# Front_left_lamp_v4.net
KiCad netlist of a schematic drawn in EAGLE
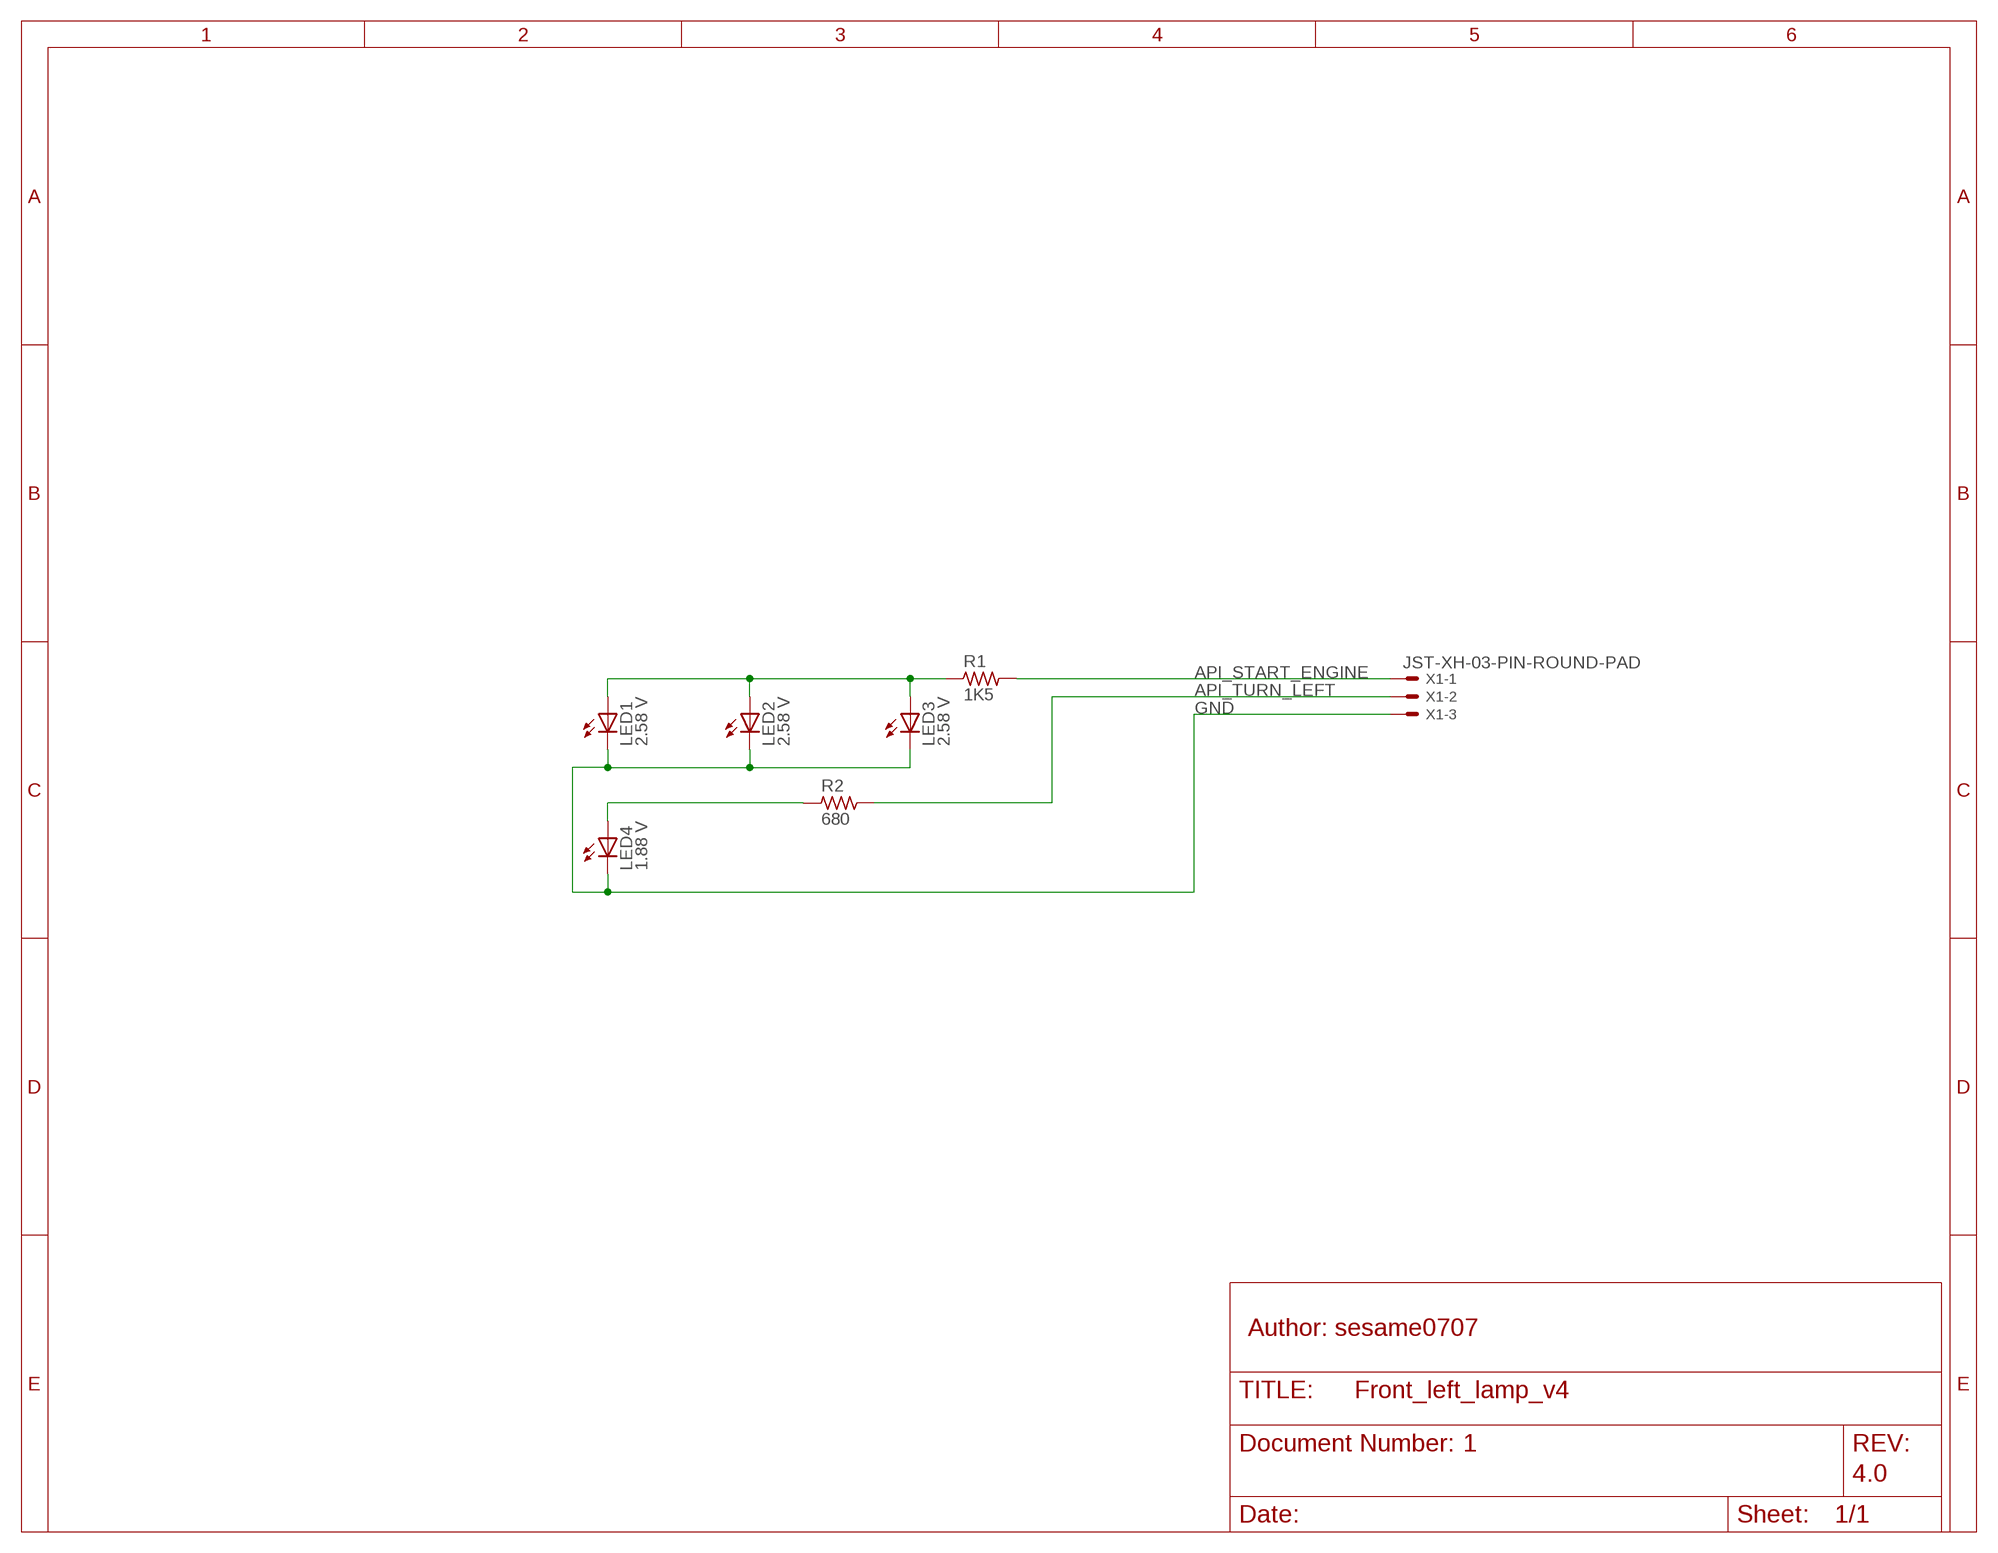
[diagram p0: schematic, sheet 1]

(export (version "E")
  (design (tool "Eeschema 10.0.6"))
  (components
    (comp (ref "LED1")
      (value "2.58 V")
      (footprint "eagle-import:LED5MM")
      (libsource (lib "eagle-import") (part "LED5MM"))
    )
    (comp (ref "LED2")
      (value "2.58 V")
      (footprint "eagle-import:LED5MM")
      (libsource (lib "eagle-import") (part "LED5MM"))
    )
    (comp (ref "LED3")
      (value "2.58 V")
      (footprint "eagle-import:LED5MM")
      (libsource (lib "eagle-import") (part "LED5MM"))
    )
    (comp (ref "LED4")
      (value "1.88 V")
      (footprint "eagle-import:LED5MM")
      (libsource (lib "eagle-import") (part "LED5MM"))
    )
    (comp (ref "R1")
      (value "1K5")
      (footprint "eagle-import:R1206")
      (libsource (lib "eagle-import") (part "R_1206"))
    )
    (comp (ref "R2")
      (value "680")
      (footprint "eagle-import:R1206")
      (libsource (lib "eagle-import") (part "R_1206"))
    )
    (comp (ref "X1")
      (value "JST-XH-03-PIN-ROUND-PAD")
      (footprint "eagle-import:JST-XH-03-PACKAGE-ROUND-PAD")
      (libsource (lib "eagle-import") (part "JST-XH-03-PIN-ROUND-PAD"))
    )
  )
  (nets
    (net (code "1") (name "/API_START_ENGINE") (class "Default")
      (node (ref "LED1") (pin "A") (pinfunction "A_A") (pintype "passive"))
      (node (ref "LED2") (pin "A") (pinfunction "A_A") (pintype "passive"))
      (node (ref "LED3") (pin "A") (pinfunction "A_A") (pintype "passive"))
      (node (ref "R1") (pin "1") (pinfunction "1_1") (pintype "passive"))
    )
    (net (code "2") (name "/API_TURN_LEFT") (class "Default")
      (node (ref "R2") (pin "2") (pinfunction "2_2") (pintype "passive"))
      (node (ref "X1") (pin "2") (pinfunction "S_2") (pintype "passive"))
    )
    (net (code "3") (name "/GND") (class "Default")
      (node (ref "LED1") (pin "K") (pinfunction "C_K") (pintype "passive"))
      (node (ref "LED2") (pin "K") (pinfunction "C_K") (pintype "passive"))
      (node (ref "LED3") (pin "K") (pinfunction "C_K") (pintype "passive"))
      (node (ref "LED4") (pin "K") (pinfunction "C_K") (pintype "passive"))
      (node (ref "X1") (pin "3") (pinfunction "S_3") (pintype "passive"))
    )
    (net (code "4") (name "Net-(LED4-PadA)") (class "Default")
      (node (ref "LED4") (pin "A") (pinfunction "A_A") (pintype "passive"))
      (node (ref "R2") (pin "1") (pinfunction "1_1") (pintype "passive"))
    )
    (net (code "5") (name "Net-(X1A-S)") (class "Default")
      (node (ref "R1") (pin "2") (pinfunction "2_2") (pintype "passive"))
      (node (ref "X1") (pin "1") (pinfunction "S_1") (pintype "passive"))
    )
  )
)
